# TPS55340_BOOST_PCB.net
KiCad netlist of a schematic drawn in Altium Designer
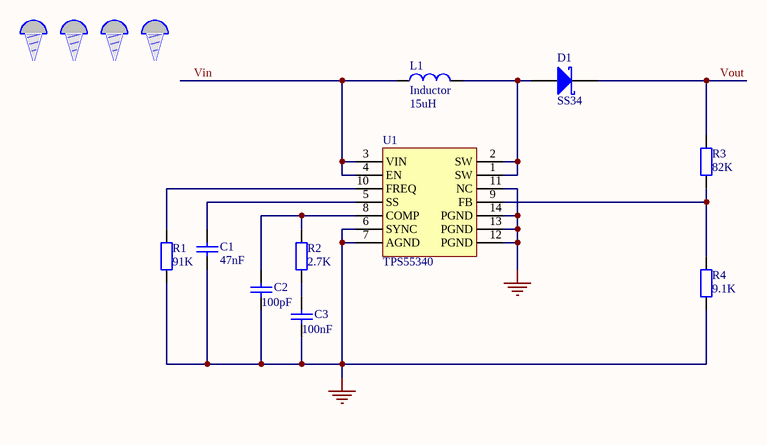
[diagram p0: TPS55340_BOOST_PCB.SchDoc]

(export (version "E")
  (design (tool "Eeschema 10.0.6"))
  (components
    (comp (ref "C1")
      (value "47nF")
      (footprint "CAPC1608N")
      (description "Capacitor")
      (fields (field (name "Comment") "Cap1") (field (name "PUBLISHER") "Altium Limited"))
      (libsource (lib "Peace的集成库") (part "Cap1"))
    )
    (comp (ref "C2")
      (value "100pF")
      (footprint "CAPC1608N")
      (description "Capacitor")
      (fields (field (name "Comment") "Cap1") (field (name "PUBLISHER") "Altium Limited"))
      (libsource (lib "Peace的集成库") (part "Cap1"))
    )
    (comp (ref "C3")
      (value "100nF")
      (footprint "CAPC1608N")
      (description "Capacitor")
      (fields (field (name "Comment") "Cap1") (field (name "PUBLISHER") "Altium Limited"))
      (libsource (lib "Peace的集成库") (part "Cap1"))
    )
    (comp (ref "D1")
      (value "SS34")
      (footprint "DO-214AC")
      (description "Schottky Diode")
      (fields (field (name "PUBLISHER") "Altium Limited"))
      (libsource (lib "Peace的集成库") (part "D Schottky"))
    )
    (comp (ref "L1")
      (value "Inductor")
      (footprint "贴片680u")
      (fields (field (name "ALTIUM_VALUE") "15uH") (field (name "PUBLISHER") "Altium Limited"))
      (libsource (lib "Peace的集成库") (part "Inductor"))
    )
    (comp (ref "M1") (value "M") (footprint "TAPPING HOLE") (libsource (lib "Peace的集成库") (part "M")))
    (comp (ref "M2") (value "M") (footprint "TAPPING HOLE") (libsource (lib "Peace的集成库") (part "M")))
    (comp (ref "M3") (value "M") (footprint "TAPPING HOLE") (libsource (lib "Peace的集成库") (part "M")))
    (comp (ref "M4") (value "M") (footprint "TAPPING HOLE") (libsource (lib "Peace的集成库") (part "M")))
    (comp (ref "R1")
      (value "91K")
      (footprint "RESC1608N")
      (description "Resistor")
      (fields (field (name "Comment") "Res1") (field (name "PUBLISHER") "Altium Limited"))
      (libsource (lib "Peace的集成库") (part "Res1"))
    )
    (comp (ref "R2")
      (value "2.7K")
      (footprint "RESC1608N")
      (description "Resistor")
      (fields (field (name "Comment") "Res1") (field (name "PUBLISHER") "Altium Limited"))
      (libsource (lib "Peace的集成库") (part "Res1"))
    )
    (comp (ref "R3")
      (value "82K")
      (footprint "RESC1608N")
      (description "Resistor")
      (fields (field (name "Comment") "Res1") (field (name "PUBLISHER") "Altium Limited"))
      (libsource (lib "Peace的集成库") (part "Res1"))
    )
    (comp (ref "R4")
      (value "9.1K")
      (footprint "RESC1608N")
      (description "Resistor")
      (fields (field (name "Comment") "Res1") (field (name "PUBLISHER") "Altium Limited"))
      (libsource (lib "Peace的集成库") (part "Res1"))
    )
    (comp (ref "U1")
      (value "TPS55340")
      (footprint "TSSOP14_L")
      (libsource (lib "Peace的集成库") (part "TPS55340"))
    )
  )
  (nets
    (net (code "1") (name "/Vin") (class "Default")
      (node (ref "L1") (pin "1") (pinfunction "1_1") (pintype "passive"))
      (node (ref "U1") (pin "3") (pinfunction "VIN_3") (pintype "passive"))
      (node (ref "U1") (pin "4") (pinfunction "EN_4") (pintype "passive"))
    )
    (net (code "2") (name "/Vout") (class "Default")
      (node (ref "D1") (pin "2") (pinfunction "K_2") (pintype "passive"))
      (node (ref "R3") (pin "2") (pinfunction "2_2") (pintype "passive"))
    )
    (net (code "3") (name "GND") (class "Default")
      (node (ref "C1") (pin "1") (pinfunction "1_1") (pintype "passive"))
      (node (ref "C2") (pin "1") (pinfunction "1_1") (pintype "passive"))
      (node (ref "C3") (pin "1") (pinfunction "1_1") (pintype "passive"))
      (node (ref "R1") (pin "1") (pinfunction "1_1") (pintype "passive"))
      (node (ref "R4") (pin "1") (pinfunction "1_1") (pintype "passive"))
      (node (ref "U1") (pin "11") (pinfunction "NC_11") (pintype "passive"))
      (node (ref "U1") (pin "12") (pinfunction "PGND_12") (pintype "passive"))
      (node (ref "U1") (pin "13") (pinfunction "PGND_13") (pintype "passive"))
      (node (ref "U1") (pin "14") (pinfunction "PGND_14") (pintype "passive"))
      (node (ref "U1") (pin "6") (pinfunction "SYNC_6") (pintype "passive"))
      (node (ref "U1") (pin "7") (pinfunction "AGND_7") (pintype "passive"))
    )
    (net (code "4") (name "Net-(C3-Pad2)") (class "Default")
      (node (ref "C3") (pin "2") (pinfunction "2_2") (pintype "passive"))
      (node (ref "R2") (pin "1") (pinfunction "1_1") (pintype "passive"))
    )
    (net (code "5") (name "Net-(D1-A)") (class "Default")
      (node (ref "D1") (pin "1") (pinfunction "A_1") (pintype "passive"))
      (node (ref "L1") (pin "2") (pinfunction "2_2") (pintype "passive"))
      (node (ref "U1") (pin "1") (pinfunction "SW_1") (pintype "passive"))
      (node (ref "U1") (pin "2") (pinfunction "SW_2") (pintype "passive"))
    )
    (net (code "6") (name "Net-(U1-COMP)") (class "Default")
      (node (ref "C2") (pin "2") (pinfunction "2_2") (pintype "passive"))
      (node (ref "R2") (pin "2") (pinfunction "2_2") (pintype "passive"))
      (node (ref "U1") (pin "8") (pinfunction "COMP_8") (pintype "passive"))
    )
    (net (code "7") (name "Net-(U1-FB)") (class "Default")
      (node (ref "R3") (pin "1") (pinfunction "1_1") (pintype "passive"))
      (node (ref "R4") (pin "2") (pinfunction "2_2") (pintype "passive"))
      (node (ref "U1") (pin "9") (pinfunction "FB_9") (pintype "passive"))
    )
    (net (code "8") (name "Net-(U1-FREQ)") (class "Default")
      (node (ref "R1") (pin "2") (pinfunction "2_2") (pintype "passive"))
      (node (ref "U1") (pin "10") (pinfunction "FREQ_10") (pintype "passive"))
    )
    (net (code "9") (name "Net-(U1-SS)") (class "Default")
      (node (ref "C1") (pin "2") (pinfunction "2_2") (pintype "passive"))
      (node (ref "U1") (pin "5") (pinfunction "SS_5") (pintype "passive"))
    )
  )
)
